# Naxida_Eyes_Up.net
KiCad netlist of a schematic drawn in Altium Designer
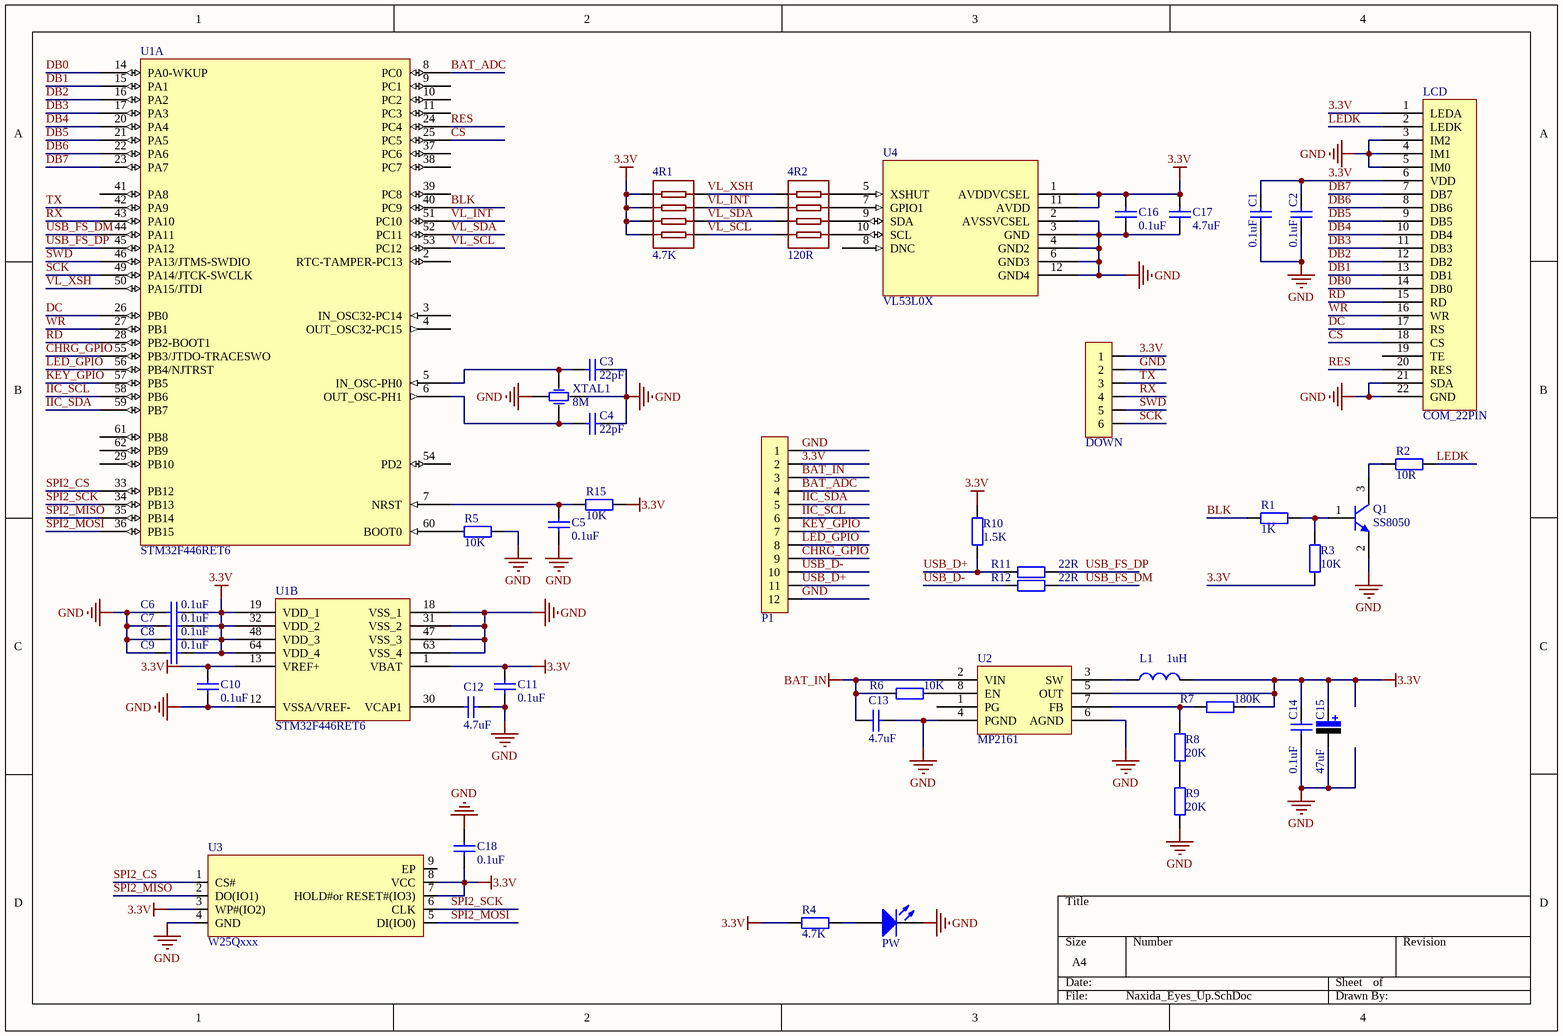
[diagram p0: Naxida_Eyes_Up.SchDoc]

(export (version "E")
  (design (tool "Eeschema 10.0.6"))
  (components
    (comp (ref "4R1") (value "4.7K") (footprint "R_4R") (libsource (lib "Zfy_Library") (part "4R")))
    (comp (ref "4R2") (value "120R") (footprint "R_4R") (libsource (lib "Zfy_Library") (part "4R")))
    (comp (ref "C1")
      (value "0.1uF")
      (footprint "LC-0603_C")
      (description "无极性电容")
      (fields (field (name "PUBLISHER") "Altium Limited"))
      (libsource (lib "Fszhang") (part "Cap"))
    )
    (comp (ref "C2")
      (value "0.1uF")
      (footprint "LC-0603_C")
      (description "无极性电容")
      (fields (field (name "PUBLISHER") "Altium Limited"))
      (libsource (lib "Fszhang") (part "Cap"))
    )
    (comp (ref "C3")
      (value "22pF")
      (footprint "LC-0603_C")
      (description "无极性电容")
      (fields (field (name "Comment") "Cap") (field (name "PUBLISHER") "Altium Limited"))
      (libsource (lib "Fszhang") (part "Cap"))
    )
    (comp (ref "C4")
      (value "22pF")
      (footprint "LC-0603_C")
      (description "无极性电容")
      (fields (field (name "Comment") "Cap") (field (name "PUBLISHER") "Altium Limited"))
      (libsource (lib "Fszhang") (part "Cap"))
    )
    (comp (ref "C5")
      (value "0.1uF")
      (footprint "LC-0603_C")
      (description "无极性电容")
      (fields (field (name "PUBLISHER") "Altium Limited"))
      (libsource (lib "Fszhang") (part "Cap"))
    )
    (comp (ref "C6")
      (value "0.1uF")
      (footprint "LC-0603_C")
      (description "无极性电容")
      (fields (field (name "PUBLISHER") "Altium Limited"))
      (libsource (lib "Fszhang") (part "Cap"))
    )
    (comp (ref "C7")
      (value "0.1uF")
      (footprint "LC-0603_C")
      (description "无极性电容")
      (fields (field (name "PUBLISHER") "Altium Limited"))
      (libsource (lib "Fszhang") (part "Cap"))
    )
    (comp (ref "C8")
      (value "0.1uF")
      (footprint "LC-0603_C")
      (description "无极性电容")
      (fields (field (name "PUBLISHER") "Altium Limited"))
      (libsource (lib "Fszhang") (part "Cap"))
    )
    (comp (ref "C9")
      (value "0.1uF")
      (footprint "LC-0603_C")
      (description "无极性电容")
      (fields (field (name "PUBLISHER") "Altium Limited"))
      (libsource (lib "Fszhang") (part "Cap"))
    )
    (comp (ref "C10")
      (value "0.1uF")
      (footprint "LC-0603_C")
      (description "无极性电容")
      (fields (field (name "PUBLISHER") "Altium Limited"))
      (libsource (lib "Fszhang") (part "Cap"))
    )
    (comp (ref "C11")
      (value "0.1uF")
      (footprint "LC-0603_C")
      (description "无极性电容")
      (fields (field (name "PUBLISHER") "Altium Limited"))
      (libsource (lib "Fszhang") (part "Cap"))
    )
    (comp (ref "C12")
      (value "4.7uF")
      (footprint "LC-0603_C")
      (description "无极性电容")
      (fields (field (name "PUBLISHER") "Altium Limited"))
      (libsource (lib "Fszhang") (part "Cap"))
    )
    (comp (ref "C13")
      (value "4.7uF")
      (footprint "LC-1206_C")
      (description "无极性电容")
      (fields (field (name "PUBLISHER") "Altium Limited"))
      (libsource (lib "Fszhang") (part "Cap"))
    )
    (comp (ref "C14")
      (value "0.1uF")
      (footprint "LC-0603_C")
      (description "无极性电容")
      (fields (field (name "PUBLISHER") "Altium Limited"))
      (libsource (lib "Fszhang") (part "Cap"))
    )
    (comp (ref "C15")
      (value "47uF")
      (footprint "CAP-3528")
      (description "极性电解电容")
      (fields (field (name "PUBLISHER") "Altium Limited"))
      (libsource (lib "Fszhang") (part "Cap Pol"))
    )
    (comp (ref "C16")
      (value "0.1uF")
      (footprint "LC-0603_C")
      (description "无极性电容")
      (fields (field (name "PUBLISHER") "Altium Limited"))
      (libsource (lib "Fszhang") (part "Cap"))
    )
    (comp (ref "C17")
      (value "4.7uF")
      (footprint "LC-0603_C")
      (description "无极性电容")
      (fields (field (name "PUBLISHER") "Altium Limited"))
      (libsource (lib "Fszhang") (part "Cap"))
    )
    (comp (ref "C18")
      (value "0.1uF")
      (footprint "LC-0603_C")
      (description "无极性电容")
      (fields (field (name "PUBLISHER") "Altium Limited"))
      (libsource (lib "Fszhang") (part "Cap"))
    )
    (comp (ref "DOWN")
      (value "Header 6*1")
      (footprint "COM_W_2.0_6P")
      (description "接插件")
      (fields (field (name "PUBLISHER") "Altium Limited"))
      (libsource (lib "Connect") (part "Header 6*1"))
    )
    (comp (ref "L1")
      (value "1uH")
      (footprint "Inductor-SWPA4030")
      (description "电感")
      (fields (field (name "Comment") "Inductor") (field (name "PUBLISHER") "Altium Limited"))
      (libsource (lib "Fszhang") (part "Inductor"))
    )
    (comp (ref "LCD")
      (value "COM_22PIN")
      (footprint "FPC_22PIN_0.5")
      (libsource (lib "Zfy_Library") (part "COM_22PIN"))
    )
    (comp (ref "P1")
      (value "Header 12*1")
      (footprint "HDR12X1_A-1.27mm")
      (description "接插件")
      (fields (field (name "PUBLISHER") "Altium Limited"))
      (libsource (lib "Connect") (part "Header 12*1"))
    )
    (comp (ref "PW")
      (value "LED0")
      (footprint "LC-0603_LED_S1")
      (description "发光二极管")
      (fields (field (name "PUBLISHER") "Altium Limited"))
      (libsource (lib "Fszhang") (part "LED0"))
    )
    (comp (ref "Q1")
      (value "SS8050")
      (footprint "SOT-23")
      (description "NPN贴片三极管")
      (fields (field (name "PUBLISHER") "Altium Limited"))
      (libsource (lib "Fszhang") (part "SS8050"))
    )
    (comp (ref "R1")
      (value "1K")
      (footprint "LC-0603_R")
      (description "贴片电阻")
      (fields (field (name "PUBLISHER") "Altium Limited"))
      (libsource (lib "") (part "=VALUE_1"))
    )
    (comp (ref "R2")
      (value "10R")
      (footprint "LC-0603_R")
      (description "贴片电阻")
      (fields (field (name "PUBLISHER") "Altium Limited"))
      (libsource (lib "") (part "=VALUE_1"))
    )
    (comp (ref "R3")
      (value "10K")
      (footprint "LC-0603_R")
      (description "贴片电阻")
      (fields (field (name "PUBLISHER") "Altium Limited"))
      (libsource (lib "Fszhang") (part "=VALUE"))
    )
    (comp (ref "R4")
      (value "4.7K")
      (footprint "LC-0603_R")
      (description "贴片电阻")
      (fields (field (name "Comment") "Res1") (field (name "PUBLISHER") "Altium Limited"))
      (libsource (lib "Fszhang") (part "Res1"))
    )
    (comp (ref "R5")
      (value "10K")
      (footprint "LC-0603_R")
      (description "贴片电阻")
      (fields (field (name "PUBLISHER") "Altium Limited"))
      (libsource (lib "") (part "=VALUE_1"))
    )
    (comp (ref "R6")
      (value "10K")
      (footprint "LC-0603_R")
      (description "贴片电阻")
      (fields (field (name "PUBLISHER") "Altium Limited"))
      (libsource (lib "") (part "=VALUE_1"))
    )
    (comp (ref "R7")
      (value "180K")
      (footprint "LC-0603_R")
      (description "贴片电阻")
      (fields (field (name "PUBLISHER") "Altium Limited"))
      (libsource (lib "") (part "=VALUE_1"))
    )
    (comp (ref "R8")
      (value "20K")
      (footprint "LC-0603_R")
      (description "贴片电阻")
      (fields (field (name "PUBLISHER") "Altium Limited"))
      (libsource (lib "Fszhang") (part "=VALUE"))
    )
    (comp (ref "R9")
      (value "20K")
      (footprint "LC-0603_R")
      (description "贴片电阻")
      (fields (field (name "PUBLISHER") "Altium Limited"))
      (libsource (lib "Fszhang") (part "=VALUE"))
    )
    (comp (ref "R10")
      (value "1.5K")
      (footprint "LC-0603_R")
      (description "贴片电阻")
      (fields (field (name "PUBLISHER") "Altium Limited"))
      (libsource (lib "Fszhang") (part "=VALUE"))
    )
    (comp (ref "R11")
      (value "22R")
      (footprint "LC-0603_R")
      (description "贴片电阻")
      (fields (field (name "PUBLISHER") "Altium Limited"))
      (libsource (lib "") (part "=VALUE_1"))
    )
    (comp (ref "R12")
      (value "22R")
      (footprint "LC-0603_R")
      (description "贴片电阻")
      (fields (field (name "PUBLISHER") "Altium Limited"))
      (libsource (lib "") (part "=VALUE_1"))
    )
    (comp (ref "R15")
      (value "10K")
      (footprint "LC-0603_R")
      (description "贴片电阻")
      (fields (field (name "PUBLISHER") "Altium Limited"))
      (libsource (lib "") (part "=VALUE_1"))
    )
    (comp (ref "U1")
      (value "STM32F446RET6")
      (footprint "LQFP64_L")
      (libsource (lib "Fszhang") (part "Y-STM32F446RET6"))
    )
    (comp (ref "U2")
      (value "MP2161")
      (footprint "SOT-23-8_MP2161")
      (libsource (lib "Zfy_Library") (part "MP2161"))
    )
    (comp (ref "U3")
      (value "W25Qxxx")
      (footprint "WSON-8_W25Qxxx")
      (libsource (lib "Zfy_Library") (part "W25Qxxx"))
    )
    (comp (ref "U4") (value "VL53L0X") (footprint "VL53L0X") (libsource (lib "Zfy_Library") (part "VL53L0X")))
    (comp (ref "XTAL1")
      (value "8M")
      (footprint "XTAL_3225_4Pin")
      (libsource (lib "Zfy_Library") (part "XTAL_5032"))
    )
  )
  (nets
    (net (code "1") (name "/BAT_ADC") (class "Default")
      (node (ref "P1") (pin "4") (pinfunction "4_4") (pintype "passive"))
      (node (ref "U1") (pin "8") (pinfunction "PC0_8") (pintype "bidirectional"))
    )
    (net (code "2") (name "/BLK") (class "Default")
      (node (ref "R1") (pin "2") (pinfunction "2_2") (pintype "passive"))
      (node (ref "U1") (pin "40") (pinfunction "PC9_40") (pintype "bidirectional"))
    )
    (net (code "3") (name "/CHRG_GPIO") (class "Default")
      (node (ref "P1") (pin "9") (pinfunction "9_9") (pintype "passive"))
      (node (ref "U1") (pin "55") (pinfunction "PB3/JTDO-TRACESWO_55") (pintype "bidirectional"))
    )
    (net (code "4") (name "/CS") (class "Default")
      (node (ref "LCD") (pin "18") (pinfunction "CS_18") (pintype "passive"))
      (node (ref "U1") (pin "25") (pinfunction "PC5_25") (pintype "bidirectional"))
    )
    (net (code "5") (name "/DB0") (class "Default")
      (node (ref "LCD") (pin "14") (pinfunction "DB0_14") (pintype "passive"))
      (node (ref "U1") (pin "14") (pinfunction "PA0-WKUP_14") (pintype "bidirectional"))
    )
    (net (code "6") (name "/DB1") (class "Default")
      (node (ref "LCD") (pin "13") (pinfunction "DB1_13") (pintype "passive"))
      (node (ref "U1") (pin "15") (pinfunction "PA1_15") (pintype "bidirectional"))
    )
    (net (code "7") (name "/DB2") (class "Default")
      (node (ref "LCD") (pin "12") (pinfunction "DB2_12") (pintype "passive"))
      (node (ref "U1") (pin "16") (pinfunction "PA2_16") (pintype "bidirectional"))
    )
    (net (code "8") (name "/DB3") (class "Default")
      (node (ref "LCD") (pin "11") (pinfunction "DB3_11") (pintype "passive"))
      (node (ref "U1") (pin "17") (pinfunction "PA3_17") (pintype "bidirectional"))
    )
    (net (code "9") (name "/DB4") (class "Default")
      (node (ref "LCD") (pin "10") (pinfunction "DB4_10") (pintype "passive"))
      (node (ref "U1") (pin "20") (pinfunction "PA4_20") (pintype "bidirectional"))
    )
    (net (code "10") (name "/DB5") (class "Default")
      (node (ref "LCD") (pin "9") (pinfunction "DB5_9") (pintype "passive"))
      (node (ref "U1") (pin "21") (pinfunction "PA5_21") (pintype "bidirectional"))
    )
    (net (code "11") (name "/DB6") (class "Default")
      (node (ref "LCD") (pin "8") (pinfunction "DB6_8") (pintype "passive"))
      (node (ref "U1") (pin "22") (pinfunction "PA6_22") (pintype "bidirectional"))
    )
    (net (code "12") (name "/DB7") (class "Default")
      (node (ref "LCD") (pin "7") (pinfunction "DB7_7") (pintype "passive"))
      (node (ref "U1") (pin "23") (pinfunction "PA7_23") (pintype "bidirectional"))
    )
    (net (code "13") (name "/DC") (class "Default")
      (node (ref "LCD") (pin "17") (pinfunction "RS_17") (pintype "passive"))
      (node (ref "U1") (pin "26") (pinfunction "PB0_26") (pintype "bidirectional"))
    )
    (net (code "14") (name "/IIC_SCL") (class "Default")
      (node (ref "P1") (pin "6") (pinfunction "6_6") (pintype "passive"))
      (node (ref "U1") (pin "58") (pinfunction "PB6_58") (pintype "bidirectional"))
    )
    (net (code "15") (name "/IIC_SDA") (class "Default")
      (node (ref "P1") (pin "5") (pinfunction "5_5") (pintype "passive"))
      (node (ref "U1") (pin "59") (pinfunction "PB7_59") (pintype "bidirectional"))
    )
    (net (code "16") (name "/KEY_GPIO") (class "Default")
      (node (ref "P1") (pin "7") (pinfunction "7_7") (pintype "passive"))
      (node (ref "U1") (pin "57") (pinfunction "PB5_57") (pintype "bidirectional"))
    )
    (net (code "17") (name "/LEDK") (class "Default")
      (node (ref "LCD") (pin "2") (pinfunction "LEDK_2") (pintype "passive"))
      (node (ref "R2") (pin "1") (pinfunction "1_1") (pintype "passive"))
    )
    (net (code "18") (name "/LED_GPIO") (class "Default")
      (node (ref "P1") (pin "8") (pinfunction "8_8") (pintype "passive"))
      (node (ref "U1") (pin "56") (pinfunction "PB4/NJTRST_56") (pintype "bidirectional"))
    )
    (net (code "19") (name "/RD") (class "Default")
      (node (ref "LCD") (pin "15") (pinfunction "RD_15") (pintype "passive"))
      (node (ref "U1") (pin "28") (pinfunction "PB2-BOOT1_28") (pintype "bidirectional"))
    )
    (net (code "20") (name "/RES") (class "Default")
      (node (ref "LCD") (pin "20") (pinfunction "RES_20") (pintype "passive"))
      (node (ref "U1") (pin "24") (pinfunction "PC4_24") (pintype "bidirectional"))
    )
    (net (code "21") (name "/RX") (class "Default")
      (node (ref "DOWN") (pin "4") (pinfunction "4_4") (pintype "passive"))
      (node (ref "U1") (pin "43") (pinfunction "PA10_43") (pintype "bidirectional"))
    )
    (net (code "22") (name "/SCK") (class "Default")
      (node (ref "DOWN") (pin "6") (pinfunction "6_6") (pintype "passive"))
      (node (ref "U1") (pin "49") (pinfunction "PA14/JTCK-SWCLK_49") (pintype "bidirectional"))
    )
    (net (code "23") (name "/SPI2_CS") (class "Default")
      (node (ref "U1") (pin "33") (pinfunction "PB12_33") (pintype "bidirectional"))
      (node (ref "U3") (pin "1") (pinfunction "CS#_1") (pintype "passive"))
    )
    (net (code "24") (name "/SPI2_MISO") (class "Default")
      (node (ref "U1") (pin "35") (pinfunction "PB14_35") (pintype "bidirectional"))
      (node (ref "U3") (pin "2") (pinfunction "DO(IO1)_2") (pintype "passive"))
    )
    (net (code "25") (name "/SPI2_MOSI") (class "Default")
      (node (ref "U1") (pin "36") (pinfunction "PB15_36") (pintype "bidirectional"))
      (node (ref "U3") (pin "5") (pinfunction "DI(IO0)_5") (pintype "passive"))
    )
    (net (code "26") (name "/SPI2_SCK") (class "Default")
      (node (ref "U1") (pin "34") (pinfunction "PB13_34") (pintype "bidirectional"))
      (node (ref "U3") (pin "6") (pinfunction "CLK_6") (pintype "passive"))
    )
    (net (code "27") (name "/SWD") (class "Default")
      (node (ref "DOWN") (pin "5") (pinfunction "5_5") (pintype "passive"))
      (node (ref "U1") (pin "46") (pinfunction "PA13/JTMS-SWDIO_46") (pintype "bidirectional"))
    )
    (net (code "28") (name "/TX") (class "Default")
      (node (ref "DOWN") (pin "3") (pinfunction "3_3") (pintype "passive"))
      (node (ref "U1") (pin "42") (pinfunction "PA9_42") (pintype "bidirectional"))
    )
    (net (code "29") (name "/USB_D+") (class "Default")
      (node (ref "P1") (pin "11") (pinfunction "11_11") (pintype "passive"))
      (node (ref "R10") (pin "2") (pinfunction "2_2") (pintype "passive"))
      (node (ref "R11") (pin "2") (pinfunction "2_2") (pintype "passive"))
    )
    (net (code "30") (name "/USB_D-") (class "Default")
      (node (ref "P1") (pin "10") (pinfunction "10_10") (pintype "passive"))
      (node (ref "R12") (pin "2") (pinfunction "2_2") (pintype "passive"))
    )
    (net (code "31") (name "/USB_FS_DM") (class "Default")
      (node (ref "R12") (pin "1") (pinfunction "1_1") (pintype "passive"))
      (node (ref "U1") (pin "44") (pinfunction "PA11_44") (pintype "bidirectional"))
    )
    (net (code "32") (name "/USB_FS_DP") (class "Default")
      (node (ref "R11") (pin "1") (pinfunction "1_1") (pintype "passive"))
      (node (ref "U1") (pin "45") (pinfunction "PA12_45") (pintype "bidirectional"))
    )
    (net (code "33") (name "/VL_INT") (class "Default")
      (node (ref "4R1") (pin "7") (pinfunction "7_7") (pintype "passive"))
      (node (ref "4R2") (pin "2") (pinfunction "2_2") (pintype "passive"))
      (node (ref "U1") (pin "51") (pinfunction "PC10_51") (pintype "bidirectional"))
    )
    (net (code "34") (name "/VL_SCL") (class "Default")
      (node (ref "4R1") (pin "5") (pinfunction "5_5") (pintype "passive"))
      (node (ref "4R2") (pin "4") (pinfunction "4_4") (pintype "passive"))
      (node (ref "U1") (pin "53") (pinfunction "PC12_53") (pintype "bidirectional"))
    )
    (net (code "35") (name "/VL_SDA") (class "Default")
      (node (ref "4R1") (pin "6") (pinfunction "6_6") (pintype "passive"))
      (node (ref "4R2") (pin "3") (pinfunction "3_3") (pintype "passive"))
      (node (ref "U1") (pin "52") (pinfunction "PC11_52") (pintype "bidirectional"))
    )
    (net (code "36") (name "/VL_XSH") (class "Default")
      (node (ref "4R1") (pin "8") (pinfunction "8_8") (pintype "passive"))
      (node (ref "4R2") (pin "1") (pinfunction "1_1") (pintype "passive"))
      (node (ref "U1") (pin "50") (pinfunction "PA15/JTDI_50") (pintype "bidirectional"))
    )
    (net (code "37") (name "/WR") (class "Default")
      (node (ref "LCD") (pin "16") (pinfunction "WR_16") (pintype "passive"))
      (node (ref "U1") (pin "27") (pinfunction "PB1_27") (pintype "bidirectional"))
    )
    (net (code "38") (name "3.3V") (class "Default")
      (node (ref "4R1") (pin "1") (pinfunction "1_1") (pintype "passive"))
      (node (ref "4R1") (pin "2") (pinfunction "2_2") (pintype "passive"))
      (node (ref "4R1") (pin "3") (pinfunction "3_3") (pintype "passive"))
      (node (ref "4R1") (pin "4") (pinfunction "4_4") (pintype "passive"))
      (node (ref "C1") (pin "2") (pinfunction "2_2") (pintype "passive"))
      (node (ref "C10") (pin "2") (pinfunction "2_2") (pintype "passive"))
      (node (ref "C11") (pin "2") (pinfunction "2_2") (pintype "passive"))
      (node (ref "C14") (pin "2") (pinfunction "2_2") (pintype "passive"))
      (node (ref "C15") (pin "1") (pinfunction "1_1") (pintype "passive"))
      (node (ref "C16") (pin "2") (pinfunction "2_2") (pintype "passive"))
      (node (ref "C17") (pin "2") (pinfunction "2_2") (pintype "passive"))
      (node (ref "C18") (pin "1") (pinfunction "1_1") (pintype "passive"))
      (node (ref "C2") (pin "2") (pinfunction "2_2") (pintype "passive"))
      (node (ref "C6") (pin "2") (pinfunction "2_2") (pintype "passive"))
      (node (ref "C7") (pin "2") (pinfunction "2_2") (pintype "passive"))
      (node (ref "C8") (pin "2") (pinfunction "2_2") (pintype "passive"))
      (node (ref "C9") (pin "2") (pinfunction "2_2") (pintype "passive"))
      (node (ref "DOWN") (pin "1") (pinfunction "1_1") (pintype "passive"))
      (node (ref "L1") (pin "2") (pinfunction "2_2") (pintype "passive"))
      (node (ref "LCD") (pin "1") (pinfunction "LEDA_1") (pintype "passive"))
      (node (ref "LCD") (pin "6") (pinfunction "VDD_6") (pintype "passive"))
      (node (ref "P1") (pin "2") (pinfunction "2_2") (pintype "passive"))
      (node (ref "R10") (pin "1") (pinfunction "1_1") (pintype "passive"))
      (node (ref "R15") (pin "1") (pinfunction "1_1") (pintype "passive"))
      (node (ref "R3") (pin "2") (pinfunction "2_2") (pintype "passive"))
      (node (ref "R4") (pin "1") (pinfunction "1_1") (pintype "passive"))
      (node (ref "R7") (pin "1") (pinfunction "1_1") (pintype "passive"))
      (node (ref "U1") (pin "1") (pinfunction "VBAT_1") (pintype "power_in"))
      (node (ref "U1") (pin "13") (pinfunction "VREF+_13") (pintype "power_in"))
      (node (ref "U1") (pin "19") (pinfunction "VDD_1_19") (pintype "power_in"))
      (node (ref "U1") (pin "32") (pinfunction "VDD_2_32") (pintype "power_in"))
      (node (ref "U1") (pin "48") (pinfunction "VDD_3_48") (pintype "power_in"))
      (node (ref "U1") (pin "64") (pinfunction "VDD_4_64") (pintype "power_in"))
      (node (ref "U2") (pin "5") (pinfunction "OUT_5") (pintype "passive"))
      (node (ref "U3") (pin "3") (pinfunction "WP#(IO2)_3") (pintype "passive"))
      (node (ref "U3") (pin "7") (pinfunction "HOLD#or_RESET#(IO3)_7") (pintype "passive"))
      (node (ref "U3") (pin "8") (pinfunction "VCC_8") (pintype "passive"))
      (node (ref "U4") (pin "1") (pinfunction "AVDDVCSEL_1") (pintype "power_in"))
      (node (ref "U4") (pin "11") (pinfunction "AVDD_11") (pintype "power_in"))
    )
    (net (code "39") (name "BAT_IN") (class "Default")
      (node (ref "C13") (pin "2") (pinfunction "2_2") (pintype "passive"))
      (node (ref "P1") (pin "3") (pinfunction "3_3") (pintype "passive"))
      (node (ref "R6") (pin "2") (pinfunction "2_2") (pintype "passive"))
      (node (ref "U2") (pin "2") (pinfunction "VIN_2") (pintype "passive"))
    )
    (net (code "40") (name "GND") (class "Default")
      (node (ref "C1") (pin "1") (pinfunction "1_1") (pintype "passive"))
      (node (ref "C10") (pin "1") (pinfunction "1_1") (pintype "passive"))
      (node (ref "C11") (pin "1") (pinfunction "1_1") (pintype "passive"))
      (node (ref "C12") (pin "1") (pinfunction "1_1") (pintype "passive"))
      (node (ref "C13") (pin "1") (pinfunction "1_1") (pintype "passive"))
      (node (ref "C14") (pin "1") (pinfunction "1_1") (pintype "passive"))
      (node (ref "C15") (pin "2") (pinfunction "2_2") (pintype "passive"))
      (node (ref "C16") (pin "1") (pinfunction "1_1") (pintype "passive"))
      (node (ref "C17") (pin "1") (pinfunction "1_1") (pintype "passive"))
      (node (ref "C18") (pin "2") (pinfunction "2_2") (pintype "passive"))
      (node (ref "C2") (pin "1") (pinfunction "1_1") (pintype "passive"))
      (node (ref "C3") (pin "2") (pinfunction "2_2") (pintype "passive"))
      (node (ref "C4") (pin "2") (pinfunction "2_2") (pintype "passive"))
      (node (ref "C5") (pin "1") (pinfunction "1_1") (pintype "passive"))
      (node (ref "C6") (pin "1") (pinfunction "1_1") (pintype "passive"))
      (node (ref "C7") (pin "1") (pinfunction "1_1") (pintype "passive"))
      (node (ref "C8") (pin "1") (pinfunction "1_1") (pintype "passive"))
      (node (ref "C9") (pin "1") (pinfunction "1_1") (pintype "passive"))
      (node (ref "DOWN") (pin "2") (pinfunction "2_2") (pintype "passive"))
      (node (ref "LCD") (pin "21") (pinfunction "SDA_21") (pintype "passive"))
      (node (ref "LCD") (pin "22") (pinfunction "GND_22") (pintype "passive"))
      (node (ref "LCD") (pin "3") (pinfunction "IM2_3") (pintype "passive"))
      (node (ref "LCD") (pin "4") (pinfunction "IM1_4") (pintype "passive"))
      (node (ref "LCD") (pin "5") (pinfunction "IM0_5") (pintype "passive"))
      (node (ref "P1") (pin "1") (pinfunction "1_1") (pintype "passive"))
      (node (ref "P1") (pin "12") (pinfunction "12_12") (pintype "passive"))
      (node (ref "PW") (pin "2") (pinfunction "K_2") (pintype "passive"))
      (node (ref "Q1") (pin "2") (pinfunction "E_2") (pintype "passive"))
      (node (ref "R5") (pin "1") (pinfunction "1_1") (pintype "passive"))
      (node (ref "R9") (pin "2") (pinfunction "2_2") (pintype "passive"))
      (node (ref "U1") (pin "12") (pinfunction "VSSA/VREF-_12") (pintype "power_in"))
      (node (ref "U1") (pin "18") (pinfunction "VSS_1_18") (pintype "power_in"))
      (node (ref "U1") (pin "31") (pinfunction "VSS_2_31") (pintype "power_in"))
      (node (ref "U1") (pin "47") (pinfunction "VSS_3_47") (pintype "power_in"))
      (node (ref "U1") (pin "63") (pinfunction "VSS_4_63") (pintype "power_in"))
      (node (ref "U2") (pin "4") (pinfunction "PGND_4") (pintype "passive"))
      (node (ref "U2") (pin "6") (pinfunction "AGND_6") (pintype "passive"))
      (node (ref "U3") (pin "4") (pinfunction "GND_4") (pintype "passive"))
      (node (ref "U4") (pin "12") (pinfunction "GND4_12") (pintype "power_in"))
      (node (ref "U4") (pin "2") (pinfunction "AVSSVCSEL_2") (pintype "power_in"))
      (node (ref "U4") (pin "3") (pinfunction "GND_3") (pintype "power_in"))
      (node (ref "U4") (pin "4") (pinfunction "GND2_4") (pintype "power_in"))
      (node (ref "U4") (pin "6") (pinfunction "GND3_6") (pintype "power_in"))
      (node (ref "XTAL1") (pin "2") (pinfunction "2_2") (pintype "passive"))
      (node (ref "XTAL1") (pin "4") (pinfunction "4_4") (pintype "passive"))
    )
    (net (code "41") (name "Net-(PW-A)") (class "Default")
      (node (ref "PW") (pin "1") (pinfunction "A_1") (pintype "passive"))
      (node (ref "R4") (pin "2") (pinfunction "2_2") (pintype "passive"))
    )
    (net (code "42") (name "Net-(Q1-B)") (class "Default")
      (node (ref "Q1") (pin "1") (pinfunction "B_1") (pintype "passive"))
      (node (ref "R1") (pin "1") (pinfunction "1_1") (pintype "passive"))
      (node (ref "R3") (pin "1") (pinfunction "1_1") (pintype "passive"))
    )
    (net (code "43") (name "Net-(Q1-C)") (class "Default")
      (node (ref "Q1") (pin "3") (pinfunction "C_3") (pintype "passive"))
      (node (ref "R2") (pin "2") (pinfunction "2_2") (pintype "passive"))
    )
    (net (code "44") (name "Net-(R8-Pad2)") (class "Default")
      (node (ref "R8") (pin "2") (pinfunction "2_2") (pintype "passive"))
      (node (ref "R9") (pin "1") (pinfunction "1_1") (pintype "passive"))
    )
    (net (code "45") (name "Net-(U1A-BOOT0)") (class "Default")
      (node (ref "R5") (pin "2") (pinfunction "2_2") (pintype "passive"))
      (node (ref "U1") (pin "60") (pinfunction "BOOT0_60") (pintype "input"))
    )
    (net (code "46") (name "Net-(U1A-IN_OSC-PH0)") (class "Default")
      (node (ref "C3") (pin "1") (pinfunction "1_1") (pintype "passive"))
      (node (ref "U1") (pin "5") (pinfunction "IN_OSC-PH0_5") (pintype "input"))
      (node (ref "XTAL1") (pin "1") (pinfunction "1_1") (pintype "passive"))
    )
    (net (code "47") (name "Net-(U1A-NRST)") (class "Default")
      (node (ref "C5") (pin "2") (pinfunction "2_2") (pintype "passive"))
      (node (ref "R15") (pin "2") (pinfunction "2_2") (pintype "passive"))
      (node (ref "U1") (pin "7") (pinfunction "NRST_7") (pintype "input"))
    )
    (net (code "48") (name "Net-(U1A-OUT_OSC-PH1)") (class "Default")
      (node (ref "C4") (pin "1") (pinfunction "1_1") (pintype "passive"))
      (node (ref "U1") (pin "6") (pinfunction "OUT_OSC-PH1_6") (pintype "output"))
      (node (ref "XTAL1") (pin "3") (pinfunction "3_3") (pintype "passive"))
    )
    (net (code "49") (name "Net-(U1B-VCAP1)") (class "Default")
      (node (ref "C12") (pin "2") (pinfunction "2_2") (pintype "passive"))
      (node (ref "U1") (pin "30") (pinfunction "VCAP1_30") (pintype "power_in"))
    )
    (net (code "50") (name "Net-(U2-EN)") (class "Default")
      (node (ref "R6") (pin "1") (pinfunction "1_1") (pintype "passive"))
      (node (ref "U2") (pin "8") (pinfunction "EN_8") (pintype "passive"))
    )
    (net (code "51") (name "Net-(U2-FB)") (class "Default")
      (node (ref "R7") (pin "2") (pinfunction "2_2") (pintype "passive"))
      (node (ref "R8") (pin "1") (pinfunction "1_1") (pintype "passive"))
      (node (ref "U2") (pin "7") (pinfunction "FB_7") (pintype "passive"))
    )
    (net (code "52") (name "Net-(U2-SW)") (class "Default")
      (node (ref "L1") (pin "1") (pinfunction "1_1") (pintype "passive"))
      (node (ref "U2") (pin "3") (pinfunction "SW_3") (pintype "passive"))
    )
    (net (code "53") (name "Net-(U4-GPIO1)") (class "Default")
      (node (ref "4R2") (pin "7") (pinfunction "7_7") (pintype "passive"))
      (node (ref "U4") (pin "7") (pinfunction "GPIO1_7") (pintype "input"))
    )
    (net (code "54") (name "Net-(U4-SCL)") (class "Default")
      (node (ref "4R2") (pin "5") (pinfunction "5_5") (pintype "passive"))
      (node (ref "U4") (pin "10") (pinfunction "SCL_10") (pintype "bidirectional"))
    )
    (net (code "55") (name "Net-(U4-SDA)") (class "Default")
      (node (ref "4R2") (pin "6") (pinfunction "6_6") (pintype "passive"))
      (node (ref "U4") (pin "9") (pinfunction "SDA_9") (pintype "bidirectional"))
    )
    (net (code "56") (name "Net-(U4-XSHUT)") (class "Default")
      (node (ref "4R2") (pin "8") (pinfunction "8_8") (pintype "passive"))
      (node (ref "U4") (pin "5") (pinfunction "XSHUT_5") (pintype "input"))
    )
    (net (code "57") (name "unconnected-(LCD-TE-Pad19)") (class "Default")
      (node (ref "LCD") (pin "19") (pinfunction "TE_19") (pintype "passive"))
    )
    (net (code "58") (name "unconnected-(U1A-IN_OSC32-PC14-Pad3)") (class "Default")
      (node (ref "U1") (pin "3") (pinfunction "IN_OSC32-PC14_3") (pintype "input"))
    )
    (net (code "59") (name "unconnected-(U1A-OUT_OSC32-PC15-Pad4)") (class "Default")
      (node (ref "U1") (pin "4") (pinfunction "OUT_OSC32-PC15_4") (pintype "output"))
    )
    (net (code "60") (name "unconnected-(U1A-PA8-Pad41)") (class "Default")
      (node (ref "U1") (pin "41") (pinfunction "PA8_41") (pintype "bidirectional"))
    )
    (net (code "61") (name "unconnected-(U1A-PB8-Pad61)") (class "Default")
      (node (ref "U1") (pin "61") (pinfunction "PB8_61") (pintype "bidirectional"))
    )
    (net (code "62") (name "unconnected-(U1A-PB9-Pad62)") (class "Default")
      (node (ref "U1") (pin "62") (pinfunction "PB9_62") (pintype "bidirectional"))
    )
    (net (code "63") (name "unconnected-(U1A-PB10-Pad29)") (class "Default")
      (node (ref "U1") (pin "29") (pinfunction "PB10_29") (pintype "bidirectional"))
    )
    (net (code "64") (name "unconnected-(U1A-PC1-Pad9)") (class "Default")
      (node (ref "U1") (pin "9") (pinfunction "PC1_9") (pintype "bidirectional"))
    )
    (net (code "65") (name "unconnected-(U1A-PC2-Pad10)") (class "Default")
      (node (ref "U1") (pin "10") (pinfunction "PC2_10") (pintype "bidirectional"))
    )
    (net (code "66") (name "unconnected-(U1A-PC3-Pad11)") (class "Default")
      (node (ref "U1") (pin "11") (pinfunction "PC3_11") (pintype "bidirectional"))
    )
    (net (code "67") (name "unconnected-(U1A-PC6-Pad37)") (class "Default")
      (node (ref "U1") (pin "37") (pinfunction "PC6_37") (pintype "bidirectional"))
    )
    (net (code "68") (name "unconnected-(U1A-PC7-Pad38)") (class "Default")
      (node (ref "U1") (pin "38") (pinfunction "PC7_38") (pintype "bidirectional"))
    )
    (net (code "69") (name "unconnected-(U1A-PC8-Pad39)") (class "Default")
      (node (ref "U1") (pin "39") (pinfunction "PC8_39") (pintype "bidirectional"))
    )
    (net (code "70") (name "unconnected-(U1A-PD2-Pad54)") (class "Default")
      (node (ref "U1") (pin "54") (pinfunction "PD2_54") (pintype "bidirectional"))
    )
    (net (code "71") (name "unconnected-(U1A-RTC-TAMPER-PC13-Pad2)") (class "Default")
      (node (ref "U1") (pin "2") (pinfunction "RTC-TAMPER-PC13_2") (pintype "bidirectional"))
    )
    (net (code "72") (name "unconnected-(U2-PG-Pad1)") (class "Default")
      (node (ref "U2") (pin "1") (pinfunction "PG_1") (pintype "passive"))
    )
    (net (code "73") (name "unconnected-(U3-EP-Pad9)") (class "Default")
      (node (ref "U3") (pin "9") (pinfunction "EP_9") (pintype "passive"))
    )
    (net (code "74") (name "unconnected-(U4-DNC-Pad8)") (class "Default")
      (node (ref "U4") (pin "8") (pinfunction "DNC_8") (pintype "input"))
    )
  )
)
